# 1_STM32WB50.net
KiCad netlist of a schematic drawn in Altium Designer
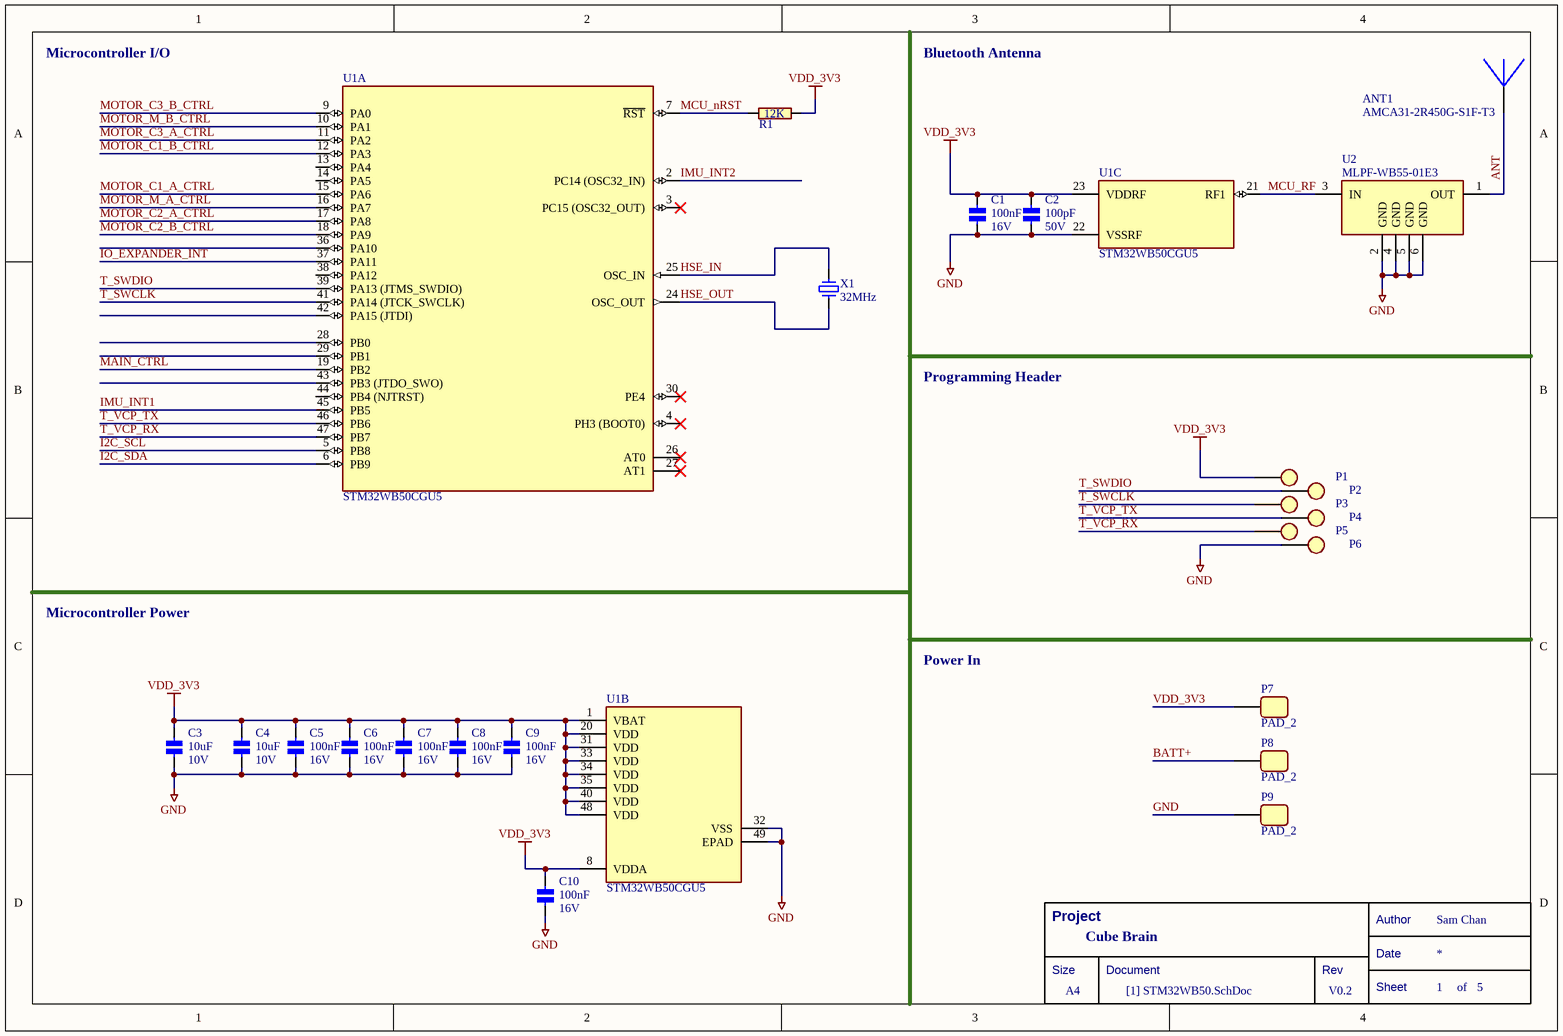
[diagram p0: [1] STM32WB50.SchDoc]

(export (version "E")
  (design (tool "Eeschema 10.0.6"))
  (components
    (comp (ref "ANT1")
      (value "AMCA31-2R450G-S1F-T3")
      (footprint "AMCA31-2R450G-S1F-T3")
      (description "RF ANT 2.4GHZ CHIP SOLDER SMD")
      (fields (field (name "MANUFACTURER") "Abracon LLC"))
      (libsource (lib "Cube Library") (part "AMCA31-2R450G-S1F-T3"))
    )
    (comp (ref "C1")
      (value "100nF")
      (footprint "CAPC0402X05N")
      (description "CAP CER 0.1UF 16V X7R 0402")
      (fields
        (field (name "MANUFACTURER") "Samsung Electro-Mechanics")
        (field (name "MANUFACTURER PART NUMBER") "CL05B104KO5NNNC")
        (field (name "CAPACITANCE") "100nF")
        (field (name "VOLTAGE - RATED") "16V")
      )
      (libsource (lib "Cube Library") (part "CER 100NF 16V"))
    )
    (comp (ref "C2")
      (value "100pF")
      (footprint "CAPC0402X05N")
      (description "CAP CER 100PF 50V C0G/NP0 0402")
      (fields
        (field (name "MANUFACTURER") "Samsung Electro-Mechanics")
        (field (name "MANUFACTURER PART NUMBER") "CL05C101JB5NNNC")
        (field (name "CAPACITANCE") "100pF")
        (field (name "VOLTAGE - RATED") "50V")
      )
      (libsource (lib "Cube Library") (part "CER 100PF 50V"))
    )
    (comp (ref "C3")
      (value "10uF")
      (footprint "CAPC0402X05N")
      (description "CAP CER 10UF 10V X5R 0402")
      (fields
        (field (name "MANUFACTURER") "Murata Electronics")
        (field (name "MANUFACTURER PART NUMBER") "GRM155R61A106ME44D")
        (field (name "CAPACITANCE") "10uF")
        (field (name "VOLTAGE - RATED") "10V")
      )
      (libsource (lib "Cube Library") (part "CER 10UF 10V"))
    )
    (comp (ref "C4")
      (value "10uF")
      (footprint "CAPC0402X05N")
      (description "CAP CER 10UF 10V X5R 0402")
      (fields
        (field (name "MANUFACTURER") "Murata Electronics")
        (field (name "MANUFACTURER PART NUMBER") "GRM155R61A106ME44D")
        (field (name "CAPACITANCE") "10uF")
        (field (name "VOLTAGE - RATED") "10V")
      )
      (libsource (lib "Cube Library") (part "CER 10UF 10V"))
    )
    (comp (ref "C5")
      (value "100nF")
      (footprint "CAPC0402X05N")
      (description "CAP CER 0.1UF 16V X7R 0402")
      (fields
        (field (name "MANUFACTURER") "Samsung Electro-Mechanics")
        (field (name "MANUFACTURER PART NUMBER") "CL05B104KO5NNNC")
        (field (name "CAPACITANCE") "100nF")
        (field (name "VOLTAGE - RATED") "16V")
      )
      (libsource (lib "Cube Library") (part "CER 100NF 16V"))
    )
    (comp (ref "C6")
      (value "100nF")
      (footprint "CAPC0402X05N")
      (description "CAP CER 0.1UF 16V X7R 0402")
      (fields
        (field (name "MANUFACTURER") "Samsung Electro-Mechanics")
        (field (name "MANUFACTURER PART NUMBER") "CL05B104KO5NNNC")
        (field (name "CAPACITANCE") "100nF")
        (field (name "VOLTAGE - RATED") "16V")
      )
      (libsource (lib "Cube Library") (part "CER 100NF 16V"))
    )
    (comp (ref "C7")
      (value "100nF")
      (footprint "CAPC0402X05N")
      (description "CAP CER 0.1UF 16V X7R 0402")
      (fields
        (field (name "MANUFACTURER") "Samsung Electro-Mechanics")
        (field (name "MANUFACTURER PART NUMBER") "CL05B104KO5NNNC")
        (field (name "CAPACITANCE") "100nF")
        (field (name "VOLTAGE - RATED") "16V")
      )
      (libsource (lib "Cube Library") (part "CER 100NF 16V"))
    )
    (comp (ref "C8")
      (value "100nF")
      (footprint "CAPC0402X05N")
      (description "CAP CER 0.1UF 16V X7R 0402")
      (fields
        (field (name "MANUFACTURER") "Samsung Electro-Mechanics")
        (field (name "MANUFACTURER PART NUMBER") "CL05B104KO5NNNC")
        (field (name "CAPACITANCE") "100nF")
        (field (name "VOLTAGE - RATED") "16V")
      )
      (libsource (lib "Cube Library") (part "CER 100NF 16V"))
    )
    (comp (ref "C9")
      (value "100nF")
      (footprint "CAPC0402X05N")
      (description "CAP CER 0.1UF 16V X7R 0402")
      (fields
        (field (name "MANUFACTURER") "Samsung Electro-Mechanics")
        (field (name "MANUFACTURER PART NUMBER") "CL05B104KO5NNNC")
        (field (name "CAPACITANCE") "100nF")
        (field (name "VOLTAGE - RATED") "16V")
      )
      (libsource (lib "Cube Library") (part "CER 100NF 16V"))
    )
    (comp (ref "C10")
      (value "100nF")
      (footprint "CAPC0402X05N")
      (description "CAP CER 0.1UF 16V X7R 0402")
      (fields
        (field (name "MANUFACTURER") "Samsung Electro-Mechanics")
        (field (name "MANUFACTURER PART NUMBER") "CL05B104KO5NNNC")
        (field (name "CAPACITANCE") "100nF")
        (field (name "VOLTAGE - RATED") "16V")
      )
      (libsource (lib "Cube Library") (part "CER 100NF 16V"))
    )
    (comp (ref "P1")
      (value "PAD_3")
      (footprint "R_PAD")
      (description "a Round Pad")
      (libsource (lib "Cube Library") (part "PAD_3"))
    )
    (comp (ref "P2")
      (value "PAD_3")
      (footprint "R_PAD")
      (description "a Round Pad")
      (libsource (lib "Cube Library") (part "PAD_3"))
    )
    (comp (ref "P3")
      (value "PAD_3")
      (footprint "R_PAD")
      (description "a Round Pad")
      (libsource (lib "Cube Library") (part "PAD_3"))
    )
    (comp (ref "P4")
      (value "PAD_3")
      (footprint "R_PAD")
      (description "a Round Pad")
      (libsource (lib "Cube Library") (part "PAD_3"))
    )
    (comp (ref "P5")
      (value "PAD_3")
      (footprint "R_PAD")
      (description "a Round Pad")
      (libsource (lib "Cube Library") (part "PAD_3"))
    )
    (comp (ref "P6")
      (value "PAD_3")
      (footprint "R_PAD")
      (description "a Round Pad")
      (libsource (lib "Cube Library") (part "PAD_3"))
    )
    (comp (ref "P7")
      (value "PAD_2")
      (footprint "BATT_PAD")
      (description "a Pad")
      (libsource (lib "Cube Library") (part "PAD_2"))
    )
    (comp (ref "P8")
      (value "PAD_2")
      (footprint "BATT_PAD")
      (description "a Pad")
      (libsource (lib "Cube Library") (part "PAD_2"))
    )
    (comp (ref "P9")
      (value "PAD_2")
      (footprint "BATT_PAD")
      (description "a Pad")
      (libsource (lib "Cube Library") (part "PAD_2"))
    )
    (comp (ref "R1")
      (value "12K")
      (footprint "RESC0402X04N")
      (description "RES SMD 12K OHM 1% 1/16W 0402")
      (fields
        (field (name "MANUFACTURER") "YAGEO")
        (field (name "MANUFACTURER PART NUMBER") "RC0402FR-0712KL")
        (field (name "RESISTANCE") "12K")
      )
      (libsource (lib "Cube Library") (part "RES 12K"))
    )
    (comp (ref "U1")
      (value "STM32WB50CGU5")
      (footprint "STM32WB50CGU5")
      (description "ULTRA-LOW-POWER DUAL CORE ARM CO")
      (fields (field (name "MANUFACTURER") "STMicroelectronics"))
      (libsource (lib "Cube Library") (part "STM32WB50CGU5"))
    )
    (comp (ref "U2")
      (value "MLPF-WB55-01E3")
      (footprint "MLPF-WB55-01E3")
      (description "RF FILTER LOW PASS 2.45GHZ 6SMD")
      (fields (field (name "MANUFACTURER") "STMicroelectronics"))
      (libsource (lib "Cube Library") (part "MLPF-WB55-01E3"))
    )
    (comp (ref "X1")
      (value "32MHz")
      (footprint "XRCGB32M000F1H01R0")
      (description "2.0X1.6X0.65MM 32MHZ CRYSTAL")
      (fields
        (field (name "MANUFACTURER") "Murata Electronics")
        (field (name "MANUFACTURER PART NUMBER") "XRCGB32M000F1H01R0")
      )
      (libsource (lib "Cube Library") (part "XRCGB32M000F1H01R0"))
    )
  )
  (nets
    (net (code "1") (name "/ANT") (class "Default")
      (node (ref "ANT1") (pin "1") (pinfunction "1_1") (pintype "passive"))
      (node (ref "U2") (pin "1") (pinfunction "OUT_1") (pintype "passive"))
    )
    (net (code "2") (name "/BATT+") (class "Default")
      (node (ref "P8") (pin "1") (pinfunction "1_1") (pintype "passive"))
    )
    (net (code "3") (name "/HSE_IN") (class "Default")
      (node (ref "U1") (pin "25") (pinfunction "OSC_IN_25") (pintype "input"))
      (node (ref "X1") (pin "3") (pinfunction "3_3") (pintype "passive"))
    )
    (net (code "4") (name "/HSE_OUT") (class "Default")
      (node (ref "U1") (pin "24") (pinfunction "OSC_OUT_24") (pintype "output"))
      (node (ref "X1") (pin "1") (pinfunction "1_1") (pintype "passive"))
    )
    (net (code "5") (name "/I2C_SCL") (class "Default")
      (node (ref "U1") (pin "5") (pinfunction "PB8_5") (pintype "bidirectional"))
    )
    (net (code "6") (name "/I2C_SDA") (class "Default")
      (node (ref "U1") (pin "6") (pinfunction "PB9_6") (pintype "bidirectional"))
    )
    (net (code "7") (name "/IMU_INT1") (class "Default")
      (node (ref "U1") (pin "45") (pinfunction "PB5_45") (pintype "bidirectional"))
    )
    (net (code "8") (name "/IMU_INT2") (class "Default")
      (node (ref "U1") (pin "2") (pinfunction "PC14_(OSC32_IN)_2") (pintype "bidirectional"))
    )
    (net (code "9") (name "/IO_EXPANDER_INT") (class "Default")
      (node (ref "U1") (pin "37") (pinfunction "PA11_37") (pintype "bidirectional"))
    )
    (net (code "10") (name "/MAIN_CTRL") (class "Default")
      (node (ref "U1") (pin "19") (pinfunction "PB2_19") (pintype "bidirectional"))
    )
    (net (code "11") (name "/MCU_RF") (class "Default")
      (node (ref "U1") (pin "21") (pinfunction "RF1_21") (pintype "bidirectional"))
      (node (ref "U2") (pin "3") (pinfunction "IN_3") (pintype "passive"))
    )
    (net (code "12") (name "/MCU_nRST") (class "Default")
      (node (ref "R1") (pin "1") (pinfunction "1_1") (pintype "passive"))
      (node (ref "U1") (pin "7") (pinfunction "~{RST}_7") (pintype "bidirectional"))
    )
    (net (code "13") (name "/MOTOR_C1_A_CTRL") (class "Default")
      (node (ref "U1") (pin "15") (pinfunction "PA6_15") (pintype "bidirectional"))
    )
    (net (code "14") (name "/MOTOR_C1_B_CTRL") (class "Default")
      (node (ref "U1") (pin "12") (pinfunction "PA3_12") (pintype "bidirectional"))
    )
    (net (code "15") (name "/MOTOR_C2_A_CTRL") (class "Default")
      (node (ref "U1") (pin "17") (pinfunction "PA8_17") (pintype "bidirectional"))
    )
    (net (code "16") (name "/MOTOR_C2_B_CTRL") (class "Default")
      (node (ref "U1") (pin "18") (pinfunction "PA9_18") (pintype "bidirectional"))
    )
    (net (code "17") (name "/MOTOR_C3_A_CTRL") (class "Default")
      (node (ref "U1") (pin "11") (pinfunction "PA2_11") (pintype "bidirectional"))
    )
    (net (code "18") (name "/MOTOR_C3_B_CTRL") (class "Default")
      (node (ref "U1") (pin "9") (pinfunction "PA0_9") (pintype "bidirectional"))
    )
    (net (code "19") (name "/MOTOR_M_A_CTRL") (class "Default")
      (node (ref "U1") (pin "16") (pinfunction "PA7_16") (pintype "bidirectional"))
    )
    (net (code "20") (name "/MOTOR_M_B_CTRL") (class "Default")
      (node (ref "U1") (pin "10") (pinfunction "PA1_10") (pintype "bidirectional"))
    )
    (net (code "21") (name "/T_SWCLK") (class "Default")
      (node (ref "P3") (pin "1") (pinfunction "1_1") (pintype "passive"))
      (node (ref "U1") (pin "41") (pinfunction "PA14_(JTCK_SWCLK)_41") (pintype "bidirectional"))
    )
    (net (code "22") (name "/T_SWDIO") (class "Default")
      (node (ref "P2") (pin "1") (pinfunction "1_1") (pintype "passive"))
      (node (ref "U1") (pin "39") (pinfunction "PA13_(JTMS_SWDIO)_39") (pintype "bidirectional"))
    )
    (net (code "23") (name "/T_VCP_RX") (class "Default")
      (node (ref "P5") (pin "1") (pinfunction "1_1") (pintype "passive"))
      (node (ref "U1") (pin "47") (pinfunction "PB7_47") (pintype "bidirectional"))
    )
    (net (code "24") (name "/T_VCP_TX") (class "Default")
      (node (ref "P4") (pin "1") (pinfunction "1_1") (pintype "passive"))
      (node (ref "U1") (pin "46") (pinfunction "PB6_46") (pintype "bidirectional"))
    )
    (net (code "25") (name "GND") (class "Default")
      (node (ref "C1") (pin "2") (pinfunction "2_2") (pintype "passive"))
      (node (ref "C10") (pin "2") (pinfunction "2_2") (pintype "passive"))
      (node (ref "C2") (pin "2") (pinfunction "2_2") (pintype "passive"))
      (node (ref "C3") (pin "2") (pinfunction "2_2") (pintype "passive"))
      (node (ref "C4") (pin "2") (pinfunction "2_2") (pintype "passive"))
      (node (ref "C5") (pin "2") (pinfunction "2_2") (pintype "passive"))
      (node (ref "C6") (pin "2") (pinfunction "2_2") (pintype "passive"))
      (node (ref "C7") (pin "2") (pinfunction "2_2") (pintype "passive"))
      (node (ref "C8") (pin "2") (pinfunction "2_2") (pintype "passive"))
      (node (ref "C9") (pin "2") (pinfunction "2_2") (pintype "passive"))
      (node (ref "P6") (pin "1") (pinfunction "1_1") (pintype "passive"))
      (node (ref "P9") (pin "1") (pinfunction "1_1") (pintype "passive"))
      (node (ref "U1") (pin "22") (pinfunction "VSSRF_22") (pintype "power_in"))
      (node (ref "U1") (pin "32") (pinfunction "VSS_32") (pintype "power_in"))
      (node (ref "U1") (pin "49") (pinfunction "EPAD_49") (pintype "passive"))
      (node (ref "U2") (pin "2") (pinfunction "GND_2") (pintype "passive"))
      (node (ref "U2") (pin "4") (pinfunction "GND_4") (pintype "passive"))
      (node (ref "U2") (pin "5") (pinfunction "GND_5") (pintype "passive"))
      (node (ref "U2") (pin "6") (pinfunction "GND_6") (pintype "passive"))
    )
    (net (code "26") (name "VDD_3V3") (class "Default")
      (node (ref "C1") (pin "1") (pinfunction "1_1") (pintype "passive"))
      (node (ref "C10") (pin "1") (pinfunction "1_1") (pintype "passive"))
      (node (ref "C2") (pin "1") (pinfunction "1_1") (pintype "passive"))
      (node (ref "C3") (pin "1") (pinfunction "1_1") (pintype "passive"))
      (node (ref "C4") (pin "1") (pinfunction "1_1") (pintype "passive"))
      (node (ref "C5") (pin "1") (pinfunction "1_1") (pintype "passive"))
      (node (ref "C6") (pin "1") (pinfunction "1_1") (pintype "passive"))
      (node (ref "C7") (pin "1") (pinfunction "1_1") (pintype "passive"))
      (node (ref "C8") (pin "1") (pinfunction "1_1") (pintype "passive"))
      (node (ref "C9") (pin "1") (pinfunction "1_1") (pintype "passive"))
      (node (ref "P1") (pin "1") (pinfunction "1_1") (pintype "passive"))
      (node (ref "P7") (pin "1") (pinfunction "1_1") (pintype "passive"))
      (node (ref "R1") (pin "2") (pinfunction "2_2") (pintype "passive"))
      (node (ref "U1") (pin "1") (pinfunction "VBAT_1") (pintype "power_in"))
      (node (ref "U1") (pin "20") (pinfunction "VDD_20") (pintype "power_in"))
      (node (ref "U1") (pin "23") (pinfunction "VDDRF_23") (pintype "power_in"))
      (node (ref "U1") (pin "31") (pinfunction "VDD_31") (pintype "power_in"))
      (node (ref "U1") (pin "33") (pinfunction "VDD_33") (pintype "power_in"))
      (node (ref "U1") (pin "34") (pinfunction "VDD_34") (pintype "power_in"))
      (node (ref "U1") (pin "35") (pinfunction "VDD_35") (pintype "power_in"))
      (node (ref "U1") (pin "40") (pinfunction "VDD_40") (pintype "power_in"))
      (node (ref "U1") (pin "48") (pinfunction "VDD_48") (pintype "power_in"))
      (node (ref "U1") (pin "8") (pinfunction "VDDA_8") (pintype "power_in"))
    )
    (net (code "27") (name "unconnected-(U1A-AT0-Pad26)") (class "Default")
      (node (ref "U1") (pin "26") (pinfunction "AT0_26") (pintype "passive+no_connect"))
    )
    (net (code "28") (name "unconnected-(U1A-AT1-Pad27)") (class "Default")
      (node (ref "U1") (pin "27") (pinfunction "AT1_27") (pintype "passive+no_connect"))
    )
    (net (code "29") (name "unconnected-(U1A-PA4-Pad13)") (class "Default")
      (node (ref "U1") (pin "13") (pinfunction "PA4_13") (pintype "bidirectional"))
    )
    (net (code "30") (name "unconnected-(U1A-PA5-Pad14)") (class "Default")
      (node (ref "U1") (pin "14") (pinfunction "PA5_14") (pintype "bidirectional"))
    )
    (net (code "31") (name "unconnected-(U1A-PA10-Pad36)") (class "Default")
      (node (ref "U1") (pin "36") (pinfunction "PA10_36") (pintype "bidirectional"))
    )
    (net (code "32") (name "unconnected-(U1A-PA12-Pad38)") (class "Default")
      (node (ref "U1") (pin "38") (pinfunction "PA12_38") (pintype "bidirectional"))
    )
    (net (code "33") (name "unconnected-(U1A-PA15_(JTDI)-Pad42)") (class "Default")
      (node (ref "U1") (pin "42") (pinfunction "PA15_(JTDI)_42") (pintype "bidirectional"))
    )
    (net (code "34") (name "unconnected-(U1A-PB0-Pad28)") (class "Default")
      (node (ref "U1") (pin "28") (pinfunction "PB0_28") (pintype "bidirectional"))
    )
    (net (code "35") (name "unconnected-(U1A-PB1-Pad29)") (class "Default")
      (node (ref "U1") (pin "29") (pinfunction "PB1_29") (pintype "bidirectional"))
    )
    (net (code "36") (name "unconnected-(U1A-PB3_(JTDO_SWO)-Pad43)") (class "Default")
      (node (ref "U1") (pin "43") (pinfunction "PB3_(JTDO_SWO)_43") (pintype "bidirectional"))
    )
    (net (code "37") (name "unconnected-(U1A-PB4_(NJTRST)-Pad44)") (class "Default")
      (node (ref "U1") (pin "44") (pinfunction "PB4_(NJTRST)_44") (pintype "bidirectional"))
    )
    (net (code "38") (name "unconnected-(U1A-PC15_(OSC32_OUT)-Pad3)") (class "Default")
      (node (ref "U1") (pin "3") (pinfunction "PC15_(OSC32_OUT)_3") (pintype "bidirectional+no_connect"))
    )
    (net (code "39") (name "unconnected-(U1A-PE4-Pad30)") (class "Default")
      (node (ref "U1") (pin "30") (pinfunction "PE4_30") (pintype "bidirectional+no_connect"))
    )
    (net (code "40") (name "unconnected-(U1A-PH3_(BOOT0)-Pad4)") (class "Default")
      (node (ref "U1") (pin "4") (pinfunction "PH3_(BOOT0)_4") (pintype "bidirectional+no_connect"))
    )
  )
)
